# Alat_pendeteksi_kebisingan.net
KiCad netlist of a schematic drawn in EAGLE
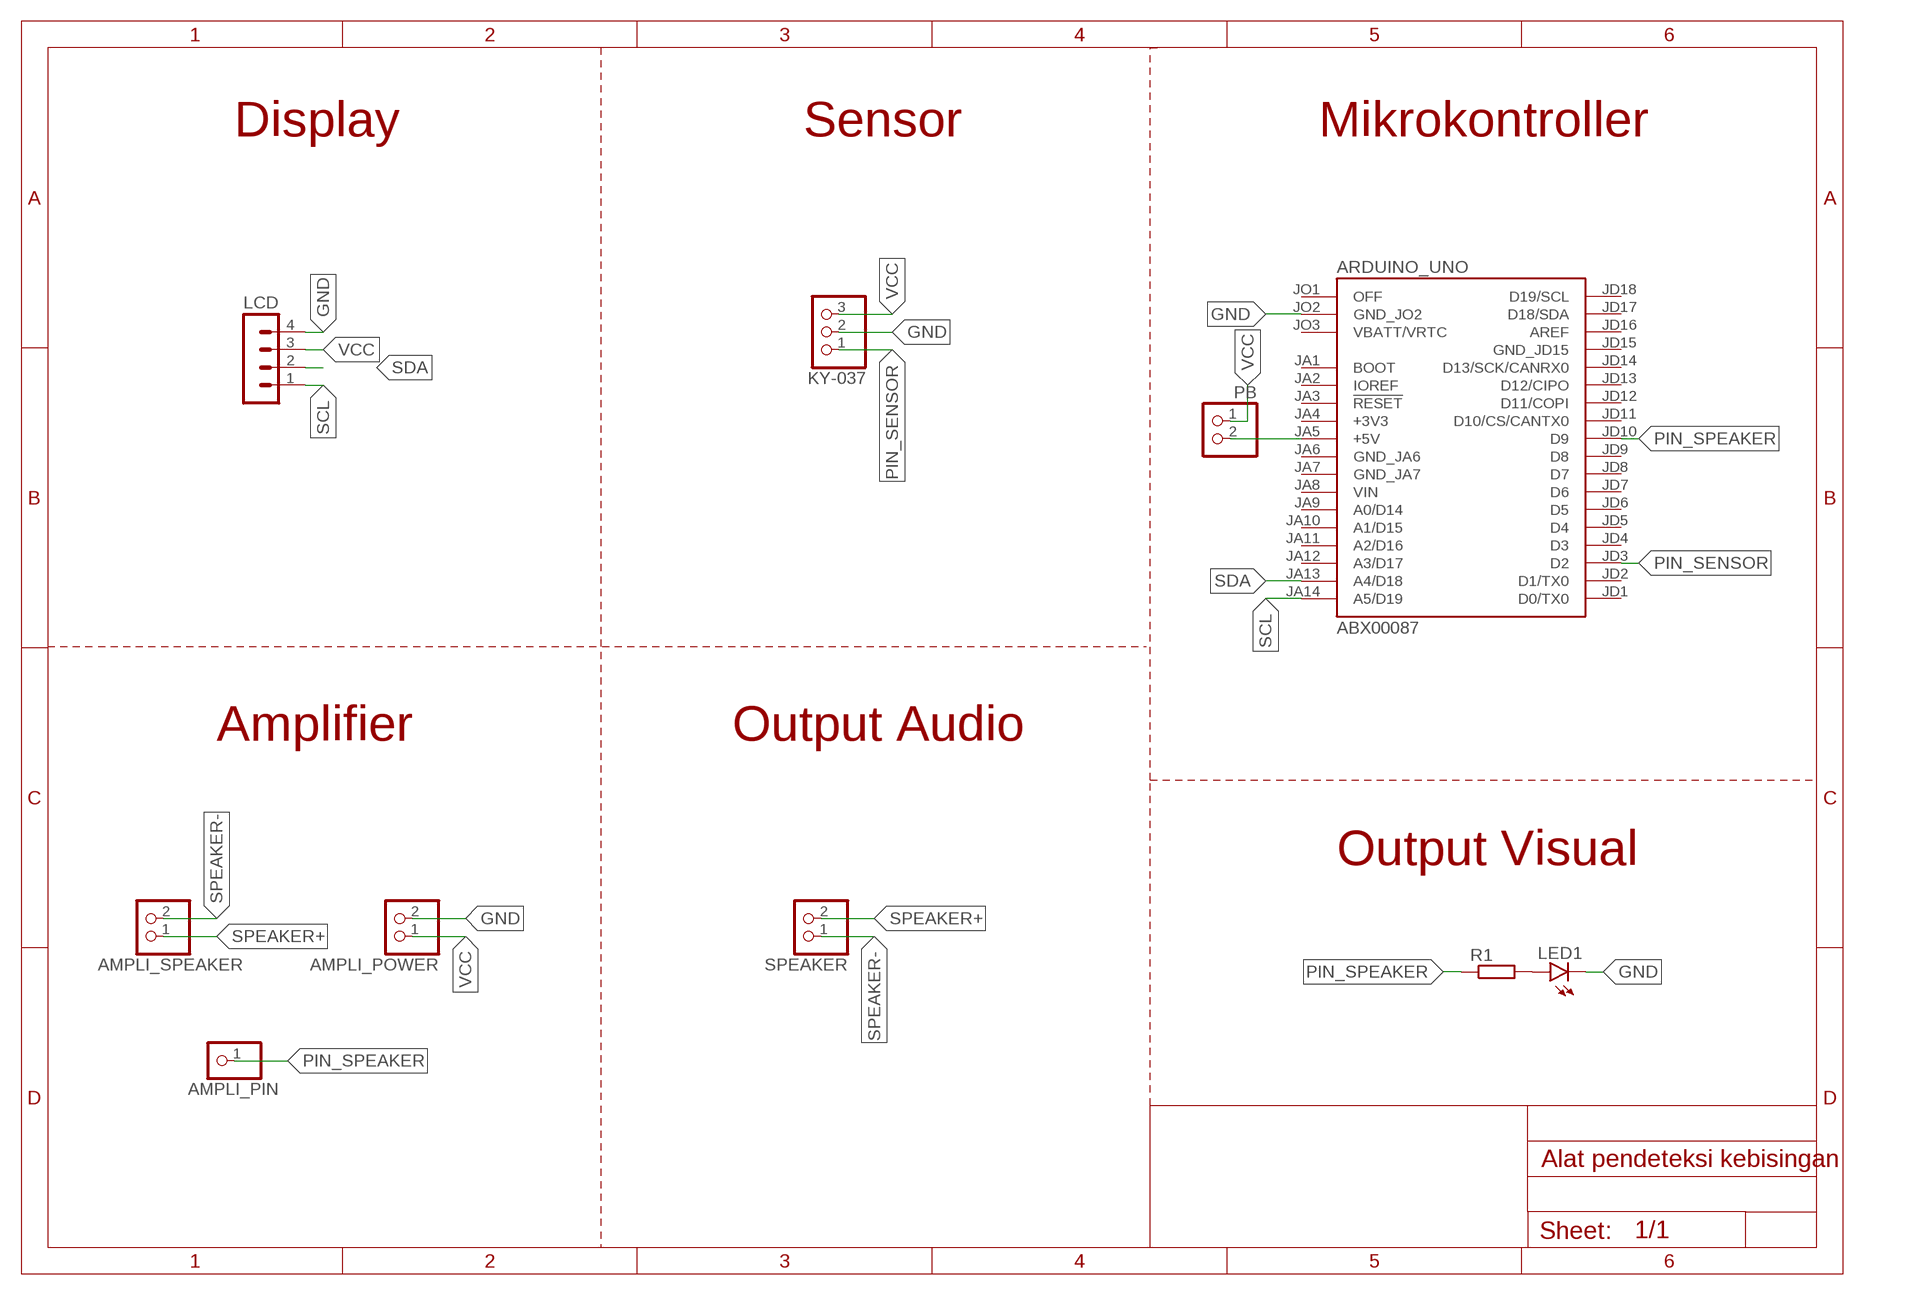
[diagram p0: schematic, sheet 1]

(export (version "E")
  (design (tool "Eeschema 10.0.6"))
  (components
    (comp (ref "AMPLI_PIN")
      (value "PINHD-1X1")
      (footprint "eagle-import:1X01")
      (libsource (lib "eagle-import") (part "PINHD-1X1"))
    )
    (comp (ref "AMPLI_POWER")
      (value "PINHD-1X2")
      (footprint "eagle-import:1X02")
      (libsource (lib "eagle-import") (part "PINHD-1X2"))
    )
    (comp (ref "AMPLI_SPEAKER")
      (value "PINHD-1X2")
      (footprint "eagle-import:1X02")
      (libsource (lib "eagle-import") (part "PINHD-1X2"))
    )
    (comp (ref "ARDUINO_UNO")
      (value "ABX00087")
      (footprint "eagle-import:MODULE_ABX00087")
      (fields (field (name "MF") "Arduino"))
      (libsource (lib "eagle-import") (part "ABX00087"))
    )
    (comp (ref "KY-037")
      (value "PINHD-1X3")
      (footprint "eagle-import:1X03")
      (libsource (lib "eagle-import") (part "PINHD-1X3"))
    )
    (comp (ref "LCD")
      (value "MA04-1")
      (footprint "eagle-import:MA04-1")
      (libsource (lib "eagle-import") (part "MA04-1"))
    )
    (comp (ref "LED1")
      (value "LED3MM")
      (footprint "eagle-import:LED3MM")
      (libsource (lib "eagle-import") (part "LED3MM"))
    )
    (comp (ref "PB")
      (value "PINHD-1X2")
      (footprint "eagle-import:1X02")
      (libsource (lib "eagle-import") (part "PINHD-1X2"))
    )
    (comp (ref "R1")
      (value "R-EU_0207/10")
      (footprint "eagle-import:0207_10")
      (libsource (lib "eagle-import") (part "R-EU_0207/10"))
    )
    (comp (ref "SPEAKER")
      (value "PINHD-1X2")
      (footprint "eagle-import:1X02")
      (libsource (lib "eagle-import") (part "PINHD-1X2"))
    )
  )
  (nets
    (net (code "1") (name "/+3V3") (class "Default")
      (node (ref "ARDUINO_UNO") (pin "JA4") (pinfunction "+3V3_JA4") (pintype "power_in"))
    )
    (net (code "2") (name "/GND_JA6") (class "Default")
      (node (ref "ARDUINO_UNO") (pin "JA6") (pinfunction "GND_JA6_JA6") (pintype "power_in"))
    )
    (net (code "3") (name "/GND_JA7") (class "Default")
      (node (ref "ARDUINO_UNO") (pin "JA7") (pinfunction "GND_JA7_JA7") (pintype "power_in"))
    )
    (net (code "4") (name "/GND_JD15") (class "Default")
      (node (ref "ARDUINO_UNO") (pin "JD15") (pinfunction "GND_JD15_JD15") (pintype "power_in"))
    )
    (net (code "5") (name "/VBATT{slash}VRTC") (class "Default")
      (node (ref "ARDUINO_UNO") (pin "JO3") (pinfunction "VBATT/VRTC_JO3") (pintype "power_in"))
    )
    (net (code "6") (name "/VIN") (class "Default")
      (node (ref "ARDUINO_UNO") (pin "JA8") (pinfunction "VIN_JA8") (pintype "power_in"))
    )
    (net (code "7") (name "GND") (class "Default")
      (node (ref "AMPLI_POWER") (pin "2") (pinfunction "2_2") (pintype "passive"))
      (node (ref "ARDUINO_UNO") (pin "JO2") (pinfunction "GND_JO2_JO2") (pintype "power_in"))
      (node (ref "KY-037") (pin "2") (pinfunction "2_2") (pintype "passive"))
      (node (ref "LCD") (pin "4") (pinfunction "4_4") (pintype "passive"))
      (node (ref "LED1") (pin "K") (pinfunction "C_K") (pintype "passive"))
    )
    (net (code "8") (name "Net-(ARDUINO_UNO-+5V)") (class "Default")
      (node (ref "ARDUINO_UNO") (pin "JA5") (pinfunction "+5V_JA5") (pintype "power_in"))
      (node (ref "PB") (pin "2") (pinfunction "2_2") (pintype "passive"))
    )
    (net (code "9") (name "Net-(LED1-PadA)") (class "Default")
      (node (ref "LED1") (pin "A") (pinfunction "A_A") (pintype "passive"))
      (node (ref "R1") (pin "2") (pinfunction "2_2") (pintype "passive"))
    )
    (net (code "10") (name "PIN_SENSOR") (class "Default")
      (node (ref "ARDUINO_UNO") (pin "JD3") (pinfunction "D2_JD3") (pintype "bidirectional"))
      (node (ref "KY-037") (pin "1") (pinfunction "1_1") (pintype "passive"))
    )
    (net (code "11") (name "PIN_SPEAKER") (class "Default")
      (node (ref "AMPLI_PIN") (pin "1") (pinfunction "1_1") (pintype "passive"))
      (node (ref "ARDUINO_UNO") (pin "JD10") (pinfunction "D9_JD10") (pintype "bidirectional"))
      (node (ref "R1") (pin "1") (pinfunction "1_1") (pintype "passive"))
    )
    (net (code "12") (name "SCL") (class "Default")
      (node (ref "ARDUINO_UNO") (pin "JA14") (pinfunction "A5/D19_JA14") (pintype "bidirectional"))
      (node (ref "LCD") (pin "1") (pinfunction "1_1") (pintype "passive"))
    )
    (net (code "13") (name "SDA") (class "Default")
      (node (ref "ARDUINO_UNO") (pin "JA13") (pinfunction "A4/D18_JA13") (pintype "bidirectional"))
      (node (ref "LCD") (pin "2") (pinfunction "2_2") (pintype "passive"))
    )
    (net (code "14") (name "SPEAKER+") (class "Default")
      (node (ref "AMPLI_SPEAKER") (pin "1") (pinfunction "1_1") (pintype "passive"))
      (node (ref "SPEAKER") (pin "2") (pinfunction "2_2") (pintype "passive"))
    )
    (net (code "15") (name "SPEAKER-") (class "Default")
      (node (ref "AMPLI_SPEAKER") (pin "2") (pinfunction "2_2") (pintype "passive"))
      (node (ref "SPEAKER") (pin "1") (pinfunction "1_1") (pintype "passive"))
    )
    (net (code "16") (name "VCC") (class "Default")
      (node (ref "AMPLI_POWER") (pin "1") (pinfunction "1_1") (pintype "passive"))
      (node (ref "KY-037") (pin "3") (pinfunction "3_3") (pintype "passive"))
      (node (ref "LCD") (pin "3") (pinfunction "3_3") (pintype "passive"))
      (node (ref "PB") (pin "1") (pinfunction "1_1") (pintype "passive"))
    )
    (net (code "17") (name "unconnected-(ARDUINO_UNO-A0{slash}D14-PadJA9)") (class "Default")
      (node (ref "ARDUINO_UNO") (pin "JA9") (pinfunction "A0/D14_JA9") (pintype "bidirectional"))
    )
    (net (code "18") (name "unconnected-(ARDUINO_UNO-A1{slash}D15-PadJA10)") (class "Default")
      (node (ref "ARDUINO_UNO") (pin "JA10") (pinfunction "A1/D15_JA10") (pintype "bidirectional"))
    )
    (net (code "19") (name "unconnected-(ARDUINO_UNO-A2{slash}D16-PadJA11)") (class "Default")
      (node (ref "ARDUINO_UNO") (pin "JA11") (pinfunction "A2/D16_JA11") (pintype "bidirectional"))
    )
    (net (code "20") (name "unconnected-(ARDUINO_UNO-A3{slash}D17-PadJA12)") (class "Default")
      (node (ref "ARDUINO_UNO") (pin "JA12") (pinfunction "A3/D17_JA12") (pintype "bidirectional"))
    )
    (net (code "21") (name "unconnected-(ARDUINO_UNO-AREF-PadJD16)") (class "Default")
      (node (ref "ARDUINO_UNO") (pin "JD16") (pinfunction "AREF_JD16") (pintype "input"))
    )
    (net (code "22") (name "unconnected-(ARDUINO_UNO-BOOT-PadJA1)") (class "Default")
      (node (ref "ARDUINO_UNO") (pin "JA1") (pinfunction "BOOT_JA1") (pintype "passive"))
    )
    (net (code "23") (name "unconnected-(ARDUINO_UNO-D0{slash}TX0-PadJD1)") (class "Default")
      (node (ref "ARDUINO_UNO") (pin "JD1") (pinfunction "D0/TX0_JD1") (pintype "bidirectional"))
    )
    (net (code "24") (name "unconnected-(ARDUINO_UNO-D1{slash}TX0-PadJD2)") (class "Default")
      (node (ref "ARDUINO_UNO") (pin "JD2") (pinfunction "D1/TX0_JD2") (pintype "bidirectional"))
    )
    (net (code "25") (name "unconnected-(ARDUINO_UNO-D3-PadJD4)") (class "Default")
      (node (ref "ARDUINO_UNO") (pin "JD4") (pinfunction "D3_JD4") (pintype "bidirectional"))
    )
    (net (code "26") (name "unconnected-(ARDUINO_UNO-D4-PadJD5)") (class "Default")
      (node (ref "ARDUINO_UNO") (pin "JD5") (pinfunction "D4_JD5") (pintype "bidirectional"))
    )
    (net (code "27") (name "unconnected-(ARDUINO_UNO-D5-PadJD6)") (class "Default")
      (node (ref "ARDUINO_UNO") (pin "JD6") (pinfunction "D5_JD6") (pintype "bidirectional"))
    )
    (net (code "28") (name "unconnected-(ARDUINO_UNO-D6-PadJD7)") (class "Default")
      (node (ref "ARDUINO_UNO") (pin "JD7") (pinfunction "D6_JD7") (pintype "bidirectional"))
    )
    (net (code "29") (name "unconnected-(ARDUINO_UNO-D7-PadJD8)") (class "Default")
      (node (ref "ARDUINO_UNO") (pin "JD8") (pinfunction "D7_JD8") (pintype "bidirectional"))
    )
    (net (code "30") (name "unconnected-(ARDUINO_UNO-D8-PadJD9)") (class "Default")
      (node (ref "ARDUINO_UNO") (pin "JD9") (pinfunction "D8_JD9") (pintype "bidirectional"))
    )
    (net (code "31") (name "unconnected-(ARDUINO_UNO-D10{slash}CS{slash}CANTX0-PadJD11)") (class "Default")
      (node (ref "ARDUINO_UNO") (pin "JD11") (pinfunction "D10/CS/CANTX0_JD11") (pintype "bidirectional"))
    )
    (net (code "32") (name "unconnected-(ARDUINO_UNO-D11{slash}COPI-PadJD12)") (class "Default")
      (node (ref "ARDUINO_UNO") (pin "JD12") (pinfunction "D11/COPI_JD12") (pintype "bidirectional"))
    )
    (net (code "33") (name "unconnected-(ARDUINO_UNO-D12{slash}CIPO-PadJD13)") (class "Default")
      (node (ref "ARDUINO_UNO") (pin "JD13") (pinfunction "D12/CIPO_JD13") (pintype "bidirectional"))
    )
    (net (code "34") (name "unconnected-(ARDUINO_UNO-D13{slash}SCK{slash}CANRX0-PadJD14)") (class "Default")
      (node (ref "ARDUINO_UNO") (pin "JD14") (pinfunction "D13/SCK/CANRX0_JD14") (pintype "bidirectional"))
    )
    (net (code "35") (name "unconnected-(ARDUINO_UNO-D18{slash}SDA-PadJD17)") (class "Default")
      (node (ref "ARDUINO_UNO") (pin "JD17") (pinfunction "D18/SDA_JD17") (pintype "bidirectional"))
    )
    (net (code "36") (name "unconnected-(ARDUINO_UNO-D19{slash}SCL-PadJD18)") (class "Default")
      (node (ref "ARDUINO_UNO") (pin "JD18") (pinfunction "D19/SCL_JD18") (pintype "bidirectional"))
    )
    (net (code "37") (name "unconnected-(ARDUINO_UNO-IOREF-PadJA2)") (class "Default")
      (node (ref "ARDUINO_UNO") (pin "JA2") (pinfunction "IOREF_JA2") (pintype "input"))
    )
    (net (code "38") (name "unconnected-(ARDUINO_UNO-OFF-PadJO1)") (class "Default")
      (node (ref "ARDUINO_UNO") (pin "JO1") (pinfunction "OFF_JO1") (pintype "input"))
    )
    (net (code "39") (name "unconnected-(ARDUINO_UNO-~{RESET}-PadJA3)") (class "Default")
      (node (ref "ARDUINO_UNO") (pin "JA3") (pinfunction "~{RESET}_JA3") (pintype "input"))
    )
  )
)
